# ProPrj_OpenHaldexC6_2025-10-16.net
KiCad netlist of a schematic drawn in EasyEDA Pro
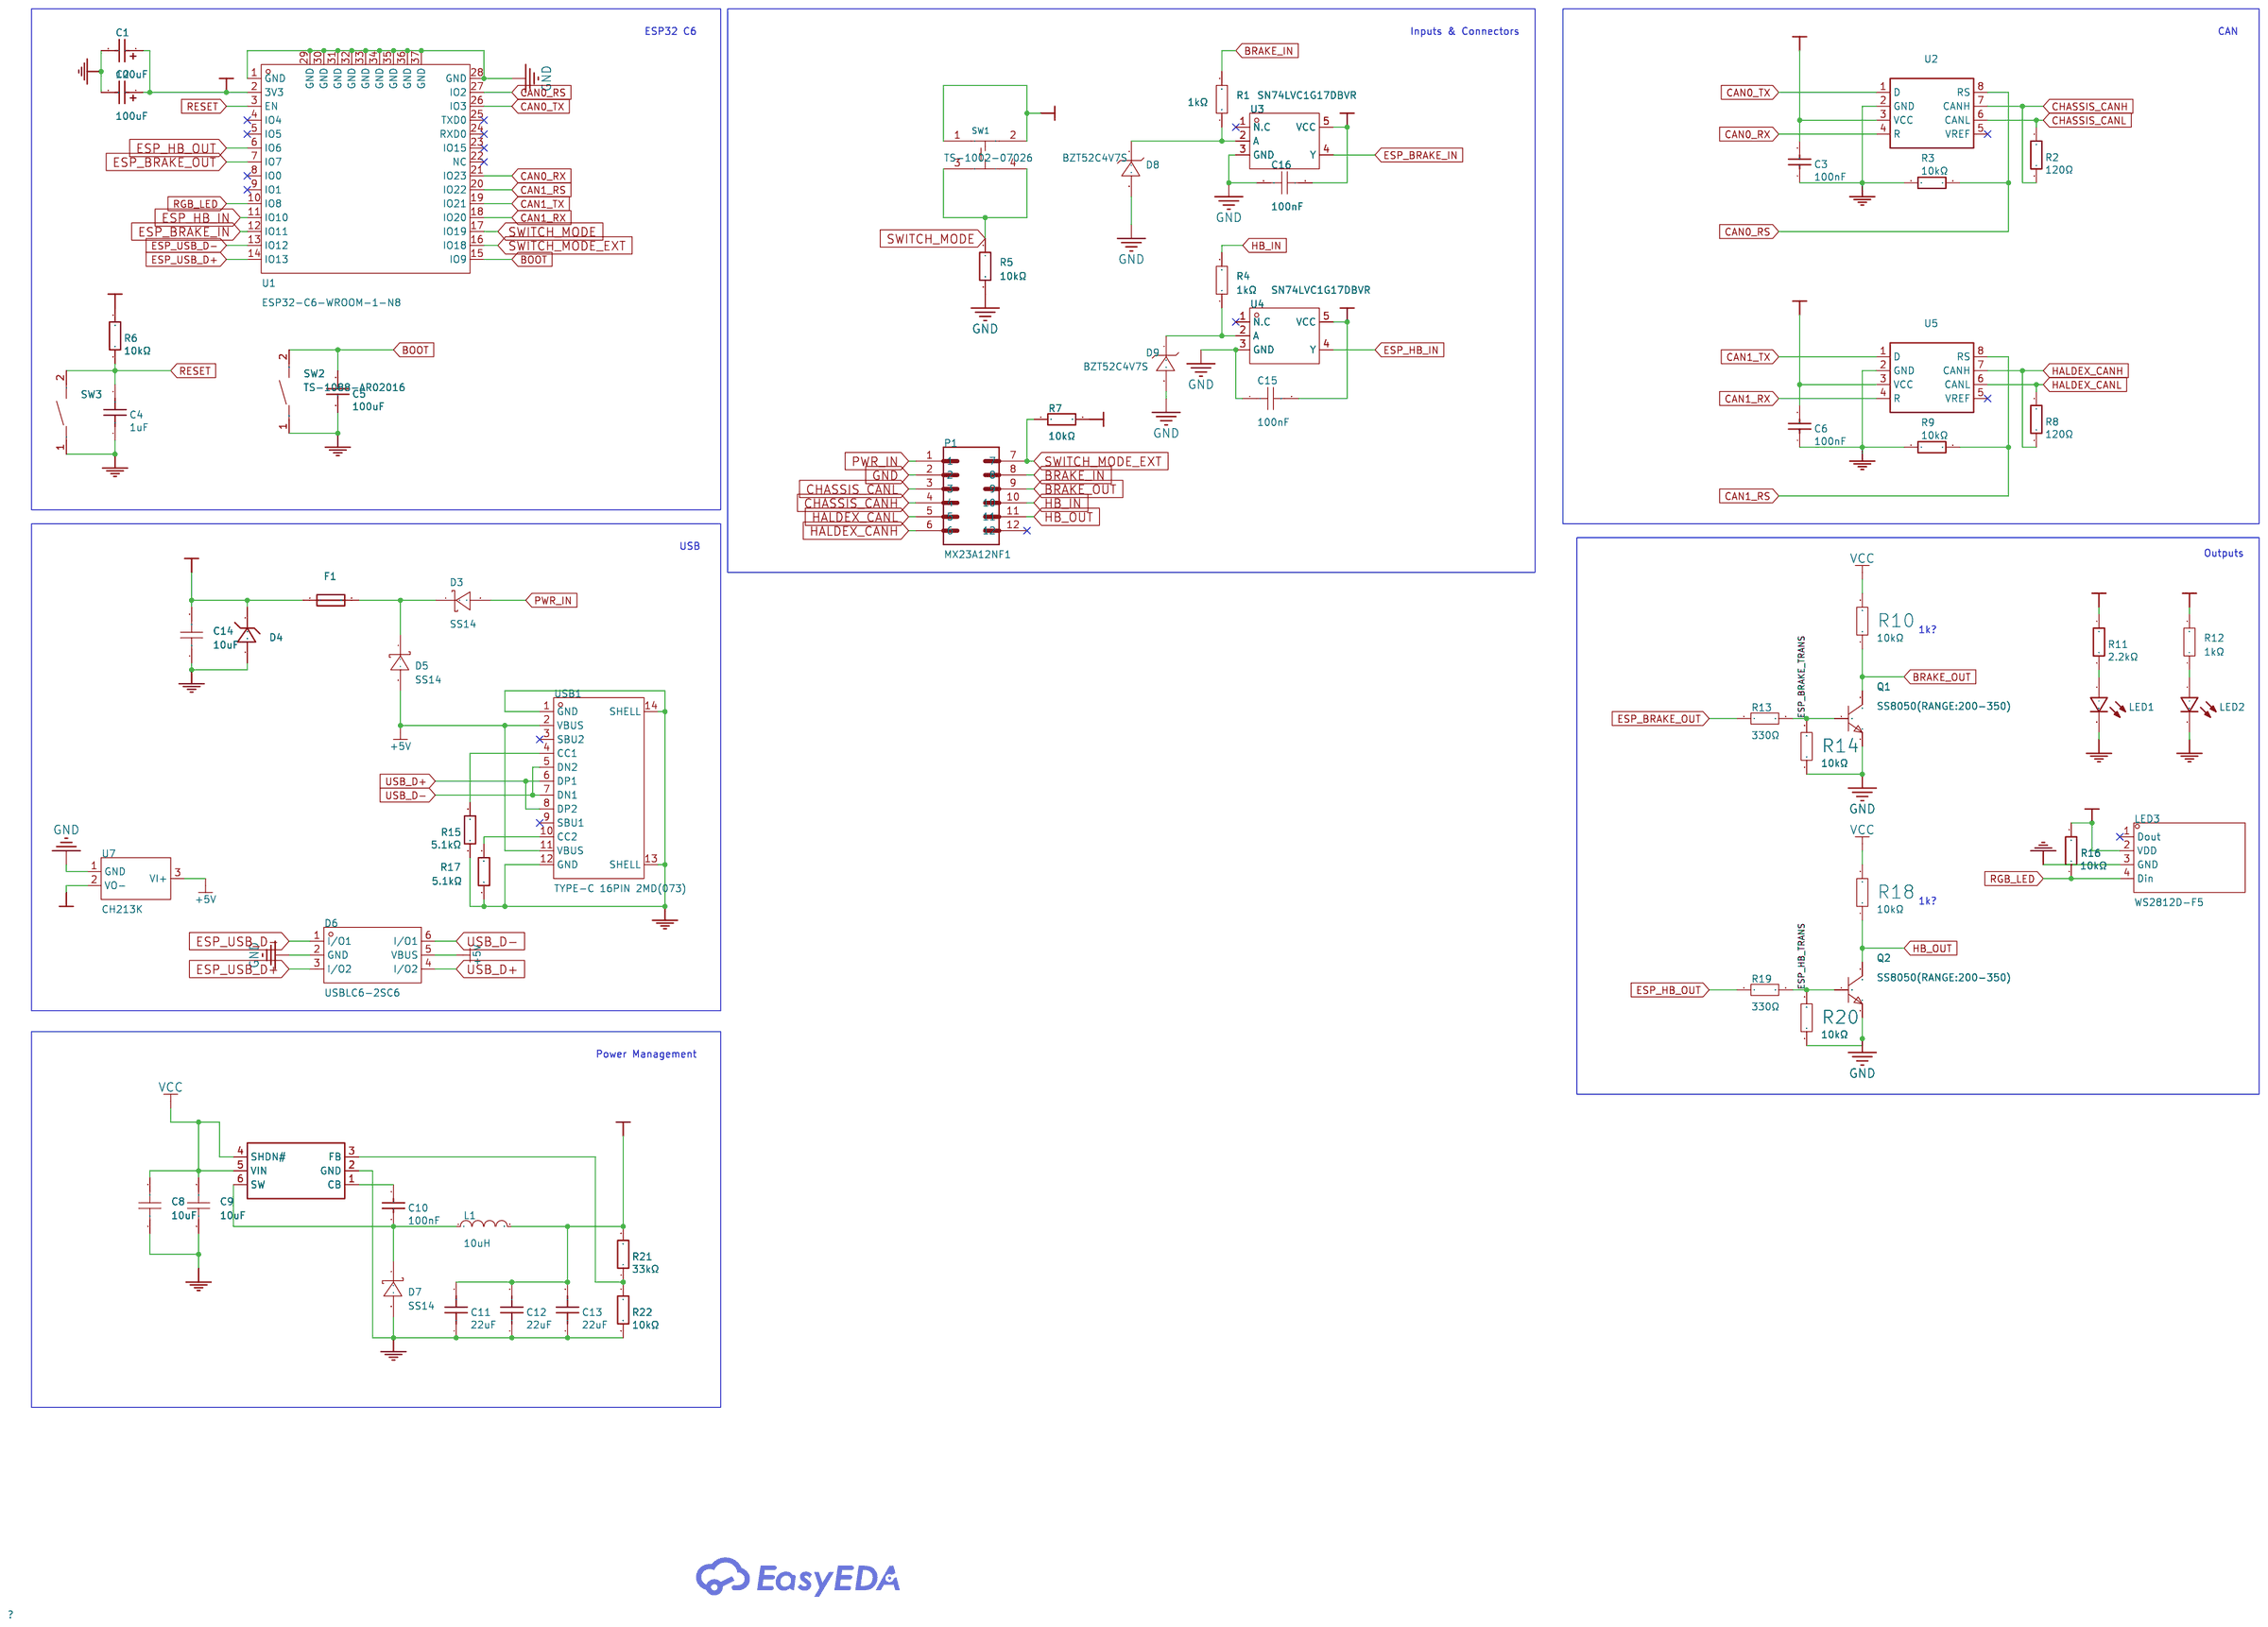
[diagram p0: schematic sheet]

(export (version "E")
  (design (tool "Eeschema 10.0.6"))
  (components
    (comp (ref "C1")
      (value "100uF")
      (fields (field (name "Manufacturer Part") "TAJB107K006RNJ") (field (name "Manufacturer") "Kyocera AVX"))
      (libsource (lib "easyedapro") (part "100uF"))
    )
    (comp (ref "C2")
      (value "100uF")
      (fields (field (name "Manufacturer Part") "TAJB107K006RNJ") (field (name "Manufacturer") "Kyocera AVX"))
      (libsource (lib "easyedapro") (part "100uF"))
    )
    (comp (ref "C3")
      (value "100nF")
      (description "Capacitance:100nF Tolerance:±10% Tolerance:±10% Voltage Rating:16V Temperature Coefficient:X7R")
      (fields (field (name "Manufacturer Part") "CL05B104KO5NNNC") (field (name "Manufacturer") "SAMSUNG"))
      (libsource (lib "easyedapro") (part "100nF"))
    )
    (comp (ref "C4")
      (value "1uF")
      (description "Capacitance:1uF Tolerance:±10% Tolerance:±10% Voltage Rating:25V Temperature Coefficient:X5R")
      (fields (field (name "Manufacturer Part") "CL05A105KA5NQNC") (field (name "Manufacturer") "SAMSUNG"))
      (libsource (lib "easyedapro") (part "1uF"))
    )
    (comp (ref "C5")
      (value "100uF")
      (fields (field (name "Manufacturer Part") "CL05B104KO5NNNC") (field (name "Manufacturer") "SAMSUNG"))
      (libsource (lib "easyedapro") (part "100nF"))
    )
    (comp (ref "C6")
      (value "100nF")
      (description "Capacitance:100nF Tolerance:±10% Tolerance:±10% Voltage Rating:16V Temperature Coefficient:X7R")
      (fields (field (name "Manufacturer Part") "CL05B104KO5NNNC") (field (name "Manufacturer") "SAMSUNG"))
      (libsource (lib "easyedapro") (part "100nF"))
    )
    (comp (ref "C8")
      (value "10uF")
      (footprint "easyedapro:C1206")
      (description "Capacitance:10uF Tolerance:±10% Tolerance:±10% Voltage Rating:35V Temperature Coefficient:-")
      (fields
        (field (name "Manufacturer Part") "CS3216X7R106K350NRI")
        (field (name "Manufacturer") "SAMWHA(三和)")
      )
      (libsource (lib "easyedapro") (part "CS3216X7R106K350NRI"))
    )
    (comp (ref "C9")
      (value "10uF")
      (footprint "easyedapro:C1206")
      (description "Capacitance:10uF Tolerance:±10% Tolerance:±10% Voltage Rating:35V Temperature Coefficient:-")
      (fields
        (field (name "Manufacturer Part") "CS3216X7R106K350NRI")
        (field (name "Manufacturer") "SAMWHA(三和)")
      )
      (libsource (lib "easyedapro") (part "CS3216X7R106K350NRI"))
    )
    (comp (ref "C10")
      (value "100nF")
      (description "Capacitance:100nF Tolerance:±10% Tolerance:±10% Voltage Rating:16V Temperature Coefficient:X7R")
      (libsource (lib "easyedapro") (part "100nF"))
    )
    (comp (ref "C11")
      (value "22uF")
      (description "Capacitance:22uF Tolerance:±20% Tolerance:±20% Voltage Rating:6.3V Temperature Coefficient:X5R")
      (libsource (lib "easyedapro") (part "22uF"))
    )
    (comp (ref "C12")
      (value "22uF")
      (description "Capacitance:22uF Tolerance:±20% Tolerance:±20% Voltage Rating:6.3V Temperature Coefficient:X5R")
      (libsource (lib "easyedapro") (part "22uF"))
    )
    (comp (ref "C13")
      (value "22uF")
      (description "Capacitance:22uF Tolerance:±20% Tolerance:±20% Voltage Rating:6.3V Temperature Coefficient:X5R")
      (libsource (lib "easyedapro") (part "22uF"))
    )
    (comp (ref "C14")
      (value "10uF")
      (footprint "easyedapro:C1206")
      (description "Capacitance:10uF Tolerance:±10% Tolerance:±10% Voltage Rating:35V Temperature Coefficient:-")
      (fields
        (field (name "Manufacturer Part") "CS3216X7R106K350NRI")
        (field (name "Manufacturer") "SAMWHA(三和)")
      )
      (libsource (lib "easyedapro") (part "CS3216X7R106K350NRI"))
    )
    (comp (ref "C15")
      (value "100nF")
      (footprint "easyedapro:C0603")
      (description "Capacitance:100nF Tolerance:±10% Tolerance:±10% Voltage Rating:50V Temperature Coefficient:X7R")
      (fields
        (field (name "Manufacturer Part") "CC0603KRX7R9BB104")
        (field (name "Manufacturer") "YAGEO(国巨)")
      )
      (libsource (lib "easyedapro") (part "CC0603KRX7R9BB104"))
    )
    (comp (ref "C16")
      (value "100nF")
      (footprint "easyedapro:C0603")
      (description "Capacitance:100nF Tolerance:±10% Tolerance:±10% Voltage Rating:50V Temperature Coefficient:X7R")
      (fields
        (field (name "Manufacturer Part") "CC0603KRX7R9BB104")
        (field (name "Manufacturer") "YAGEO(国巨)")
      )
      (libsource (lib "easyedapro") (part "CC0603KRX7R9BB104"))
    )
    (comp (ref "D3")
      (value "SS14")
      (footprint "easyedapro:SMA_L4.2-W2.6-LS5.0-RD_1")
      (fields (field (name "Manufacturer") "MDD(辰达半导体)"))
      (libsource (lib "easyedapro") (part "SS14"))
    )
    (comp (ref "D4")
      (value "SMF30A")
      (fields (field (name "Manufacturer") "DOWO"))
      (libsource (lib "easyedapro") (part "SMF30A"))
    )
    (comp (ref "D5")
      (value "SS14")
      (footprint "easyedapro:SMA_L4.2-W2.6-LS5.0-RD_1")
      (fields (field (name "Manufacturer") "MDD(辰达半导体)"))
      (libsource (lib "easyedapro") (part "SS14"))
    )
    (comp (ref "D6")
      (value "USBLC6-2SC6")
      (footprint "easyedapro:SOT-23-6_L2.9-W1.6-P0.95-LS2.8-BL")
      (description "Maximum Clamping Voltage:15V Breakdown Voltage:6V Number of Lines:双路 Type:ESD")
      (fields (field (name "Manufacturer") "UMW(友台半导体)"))
      (libsource (lib "easyedapro") (part "USBLC6-2SC6_C2687116"))
    )
    (comp (ref "D7")
      (value "SS14")
      (footprint "easyedapro:SMA_L4.2-W2.6-LS5.0-RD_1")
      (fields (field (name "Manufacturer") "MDD(辰达半导体)"))
      (libsource (lib "easyedapro") (part "SS14"))
    )
    (comp (ref "D8")
      (value "BZT52C4V7S")
      (footprint "easyedapro:SOD-323_L1.8-W1.3-LS2.5-RD")
      (fields (field (name "Manufacturer") "晶导微电子"))
      (libsource (lib "easyedapro") (part "BZT52C4V7S_C353517"))
    )
    (comp (ref "D9")
      (value "BZT52C4V7S")
      (footprint "easyedapro:SOD-323_L1.8-W1.3-LS2.5-RD")
      (fields (field (name "Manufacturer") "晶导微电子"))
      (libsource (lib "easyedapro") (part "BZT52C4V7S_C353517"))
    )
    (comp (ref "F1")
      (value "MF-MSMF110/16-2")
      (fields (field (name "Manufacturer") "BOURNS"))
      (libsource (lib "easyedapro") (part "MF-MSMF110/16-2"))
    )
    (comp (ref "L1")
      (value "10uH")
      (footprint "easyedapro:IND-SMD_L6.0-W6.0_FNR60XXS")
      (fields (field (name "Manufacturer Part") "FNR6045S100MT") (field (name "Manufacturer") "cjiang(长江微电)"))
      (libsource (lib "easyedapro") (part "FNR6045S100MT"))
    )
    (comp (ref "LED1")
      (value "19-217/GHC-YR1S2/3T")
      (fields (field (name "Manufacturer") "EVERLIGHT"))
      (libsource (lib "easyedapro") (part "19-217/GHC-YR1S2/3T"))
    )
    (comp (ref "LED2")
      (value "19-217/GHC-YR1S2/3T")
      (fields (field (name "Manufacturer") "EVERLIGHT"))
      (libsource (lib "easyedapro") (part "19-217/GHC-YR1S2/3T"))
    )
    (comp (ref "LED3")
      (value "WS2812D-F5")
      (footprint "easyedapro:LED-TH_4P-BD5.8-P1.30")
      (fields (field (name "Manufacturer") "worldsemi"))
      (libsource (lib "easyedapro") (part "WS2812D-F5"))
    )
    (comp (ref "P1")
      (value "MX23A12NF1")
      (fields (field (name "Manufacturer") "JAE(日本航空电子)"))
      (libsource (lib "easyedapro") (part "MX23A12NF1_MX23A12NF1_"))
    )
    (comp (ref "Q1")
      (value "SS8050(RANGE:200-350)")
      (footprint "easyedapro:SOT-23-3_L2.9-W1.3-P1.90-LS2.4-BR")
      (fields (field (name "Manufacturer") "CJ(江苏长电/长晶)"))
      (libsource (lib "easyedapro") (part "SS8050_C2150"))
    )
    (comp (ref "Q2")
      (value "SS8050(RANGE:200-350)")
      (footprint "easyedapro:SOT-23-3_L2.9-W1.3-P1.90-LS2.4-BR")
      (fields (field (name "Manufacturer") "CJ(江苏长电/长晶)"))
      (libsource (lib "easyedapro") (part "SS8050_C2150"))
    )
    (comp (ref "R1")
      (value "1kΩ")
      (footprint "easyedapro:R0603")
      (fields
        (field (name "Manufacturer Part") "0603WAF1001T5E")
        (field (name "Manufacturer") "UNI-ROYAL(厚声)")
      )
      (libsource (lib "easyedapro") (part "0603WAF1001T5E"))
    )
    (comp (ref "R2")
      (value "120Ω")
      (fields (field (name "Manufacturer Part") "RTT061200FTP") (field (name "Manufacturer") "RALEC"))
      (libsource (lib "easyedapro") (part "120"))
    )
    (comp (ref "R3")
      (value "10kΩ")
      (fields (field (name "Manufacturer Part") "0402WGF1002TCE") (field (name "Manufacturer") "UniOhm"))
      (libsource (lib "") (part "10K_2"))
    )
    (comp (ref "R4")
      (value "1kΩ")
      (footprint "easyedapro:R0603")
      (fields
        (field (name "Manufacturer Part") "0603WAF1001T5E")
        (field (name "Manufacturer") "UNI-ROYAL(厚声)")
      )
      (libsource (lib "easyedapro") (part "0603WAF1001T5E"))
    )
    (comp (ref "R5")
      (value "10kΩ")
      (fields (field (name "Manufacturer Part") "0402WGF1002TCE") (field (name "Manufacturer") "UniOhm"))
      (libsource (lib "easyedapro") (part "10K"))
    )
    (comp (ref "R6")
      (value "10kΩ")
      (fields (field (name "Manufacturer Part") "0402WGF1002TCE") (field (name "Manufacturer") "UniOhm"))
      (libsource (lib "easyedapro") (part "10K"))
    )
    (comp (ref "R7")
      (value "10kΩ")
      (fields (field (name "Manufacturer Part") "0402WGF1002TCE") (field (name "Manufacturer") "UniOhm"))
      (libsource (lib "easyedapro") (part "10K"))
    )
    (comp (ref "R8")
      (value "120Ω")
      (fields (field (name "Manufacturer Part") "RTT061200FTP") (field (name "Manufacturer") "RALEC"))
      (libsource (lib "easyedapro") (part "120"))
    )
    (comp (ref "R9")
      (value "10kΩ")
      (fields (field (name "Manufacturer Part") "0402WGF1002TCE") (field (name "Manufacturer") "UniOhm"))
      (libsource (lib "") (part "10K_2"))
    )
    (comp (ref "R10")
      (value "10kΩ")
      (footprint "easyedapro:R0603")
      (fields
        (field (name "Manufacturer Part") "0603WAF1002T5E")
        (field (name "Manufacturer") "UNI-ROYAL(厚声)")
      )
      (libsource (lib "easyedapro") (part "0603WAF1002T5E"))
    )
    (comp (ref "R11")
      (value "2.2kΩ")
      (fields (field (name "Manufacturer Part") "0402WGF2201TCE") (field (name "Manufacturer") "UniOhm"))
      (libsource (lib "easyedapro") (part "2.2K"))
    )
    (comp (ref "R12")
      (value "1kΩ")
      (footprint "easyedapro:R0402")
      (fields
        (field (name "Manufacturer Part") "0402WGF1001TCE")
        (field (name "Manufacturer") "UNI-ROYAL(厚声)")
      )
      (libsource (lib "easyedapro") (part "0402WGF1001TCE"))
    )
    (comp (ref "R13")
      (value "330Ω")
      (footprint "easyedapro:R0603")
      (fields
        (field (name "Manufacturer Part") "0603WAF3300T5E")
        (field (name "Manufacturer") "UNI-ROYAL(厚声)")
      )
      (libsource (lib "easyedapro") (part "0603WAF3300T5E"))
    )
    (comp (ref "R14")
      (value "10kΩ")
      (footprint "easyedapro:R0603")
      (fields
        (field (name "Manufacturer Part") "0603WAF1002T5E")
        (field (name "Manufacturer") "UNI-ROYAL(厚声)")
      )
      (libsource (lib "easyedapro") (part "0603WAF1002T5E"))
    )
    (comp (ref "R15")
      (value "5.1kΩ")
      (fields (field (name "Manufacturer Part") "0402WGF5101TCE") (field (name "Manufacturer") "UniOhm"))
      (libsource (lib "easyedapro") (part "5.1K"))
    )
    (comp (ref "R16")
      (value "10kΩ")
      (fields (field (name "Manufacturer Part") "0402WGF1002TCE") (field (name "Manufacturer") "UniOhm"))
      (libsource (lib "easyedapro") (part "10K"))
    )
    (comp (ref "R17")
      (value "5.1kΩ")
      (fields (field (name "Manufacturer Part") "0402WGF5101TCE") (field (name "Manufacturer") "UniOhm"))
      (libsource (lib "easyedapro") (part "5.1K"))
    )
    (comp (ref "R18")
      (value "10kΩ")
      (footprint "easyedapro:R0603")
      (fields
        (field (name "Manufacturer Part") "0603WAF1002T5E")
        (field (name "Manufacturer") "UNI-ROYAL(厚声)")
      )
      (libsource (lib "easyedapro") (part "0603WAF1002T5E"))
    )
    (comp (ref "R19")
      (value "330Ω")
      (footprint "easyedapro:R0603")
      (fields
        (field (name "Manufacturer Part") "0603WAF3300T5E")
        (field (name "Manufacturer") "UNI-ROYAL(厚声)")
      )
      (libsource (lib "easyedapro") (part "0603WAF3300T5E"))
    )
    (comp (ref "R20")
      (value "10kΩ")
      (footprint "easyedapro:R0603")
      (fields
        (field (name "Manufacturer Part") "0603WAF1002T5E")
        (field (name "Manufacturer") "UNI-ROYAL(厚声)")
      )
      (libsource (lib "easyedapro") (part "0603WAF1002T5E"))
    )
    (comp (ref "R21") (value "33kΩ") (libsource (lib "easyedapro") (part "33K")))
    (comp (ref "R22") (value "10kΩ") (libsource (lib "") (part "10K_1")))
    (comp (ref "SW1")
      (value "TS-1002-07026")
      (footprint "easyedapro:SW-TH_4P-L6.0-W6.0-P4.50-LS6.5")
      (fields (field (name "Manufacturer") "XUNPU(讯普)"))
      (libsource (lib "easyedapro") (part "TS-1002-07026"))
    )
    (comp (ref "SW2")
      (value "TS-1088-AR02016")
      (footprint "easyedapro:SW-SMD_L3.9-W3.0-P4.45")
      (fields (field (name "Manufacturer") "XUNPU(讯普)"))
      (libsource (lib "easyedapro") (part "TS-1088-AR02016"))
    )
    (comp (ref "SW3")
      (value "TS-1088-AR02016")
      (footprint "easyedapro:SW-SMD_L3.9-W3.0-P4.45")
      (fields (field (name "Manufacturer") "XUNPU(讯普)"))
      (libsource (lib "easyedapro") (part "TS-1088-AR02016"))
    )
    (comp (ref "U1")
      (value "ESP32-C6-WROOM-1-N8")
      (footprint "easyedapro:WIRELM-SMD_ESP32-C6-WROOM-1")
      (fields (field (name "Manufacturer") "ESPRESSIF(乐鑫)"))
      (libsource (lib "easyedapro") (part "ESP32-C6-WROOM-1-N8"))
    )
    (comp (ref "U2")
      (value "SN65HVD230DR")
      (fields (field (name "Manufacturer") "TI"))
      (libsource (lib "easyedapro") (part "SN65HVD230DR"))
    )
    (comp (ref "U3")
      (value "SN74LVC1G17DBVR")
      (footprint "easyedapro:SOT-23-5_L3.0-W1.5-P0.95-LS2.8-BL")
      (fields (field (name "Manufacturer") "TECH PUBLIC(台舟)"))
      (libsource (lib "easyedapro") (part "SN74LVC1G17DBVR_C19829662"))
    )
    (comp (ref "U4")
      (value "SN74LVC1G17DBVR")
      (footprint "easyedapro:SOT-23-5_L3.0-W1.5-P0.95-LS2.8-BL")
      (fields (field (name "Manufacturer") "TECH PUBLIC(台舟)"))
      (libsource (lib "easyedapro") (part "SN74LVC1G17DBVR_C19829662"))
    )
    (comp (ref "U5")
      (value "SN65HVD230DR")
      (fields (field (name "Manufacturer") "TI"))
      (libsource (lib "easyedapro") (part "SN65HVD230DR"))
    )
    (comp (ref "U6") (value "LMR14006XDDCR") (libsource (lib "easyedapro") (part "LMR14006XDDCR")))
    (comp (ref "U7")
      (value "CH213K")
      (footprint "easyedapro:SOT-23-3_L2.9-W1.6-P1.90-LS2.8-BR")
      (fields (field (name "Manufacturer") "WCH(南京沁恒)"))
      (libsource (lib "easyedapro") (part "CH213K"))
    )
    (comp (ref "USB1")
      (value "TYPE-C 16PIN 2MD(073)")
      (footprint "easyedapro:USB-C-SMD_TYPE-C-6PIN-2MD-073")
      (fields (field (name "Manufacturer") "SHOU HAN(首韩)"))
      (libsource (lib "easyedapro") (part "TYPE-C 16PIN 2MD(073)"))
    )
  )
  (nets
    (net (code "1") (name "+5V") (class "Default")
      (node (ref "D5") (pin "2") (pinfunction "A_2") (pintype "unspecified"))
      (node (ref "D6") (pin "5") (pinfunction "VBUS_5") (pintype "unspecified"))
      (node (ref "U7") (pin "3") (pinfunction "VI+_3") (pintype "unspecified"))
      (node (ref "USB1") (pin "11") (pinfunction "VBUS_11") (pintype "unspecified"))
      (node (ref "USB1") (pin "2") (pinfunction "VBUS_2") (pintype "unspecified"))
    )
    (net (code "2") (name "/ESP_BRAKE_TRANS") (class "Default")
      (node (ref "Q1") (pin "1") (pinfunction "B_1") (pintype "unspecified"))
      (node (ref "R13") (pin "2") (pinfunction "2_2") (pintype "input"))
      (node (ref "R14") (pin "2") (pinfunction "2_2") (pintype "input"))
    )
    (net (code "3") (name "/ESP_HB_TRANS") (class "Default")
      (node (ref "Q2") (pin "1") (pinfunction "B_1") (pintype "unspecified"))
      (node (ref "R19") (pin "2") (pinfunction "2_2") (pintype "input"))
      (node (ref "R20") (pin "2") (pinfunction "2_2") (pintype "input"))
    )
    (net (code "4") (name "3V3") (class "Default")
      (node (ref "C1") (pin "1") (pinfunction "1_1") (pintype "input"))
      (node (ref "C11") (pin "2") (pinfunction "2_2") (pintype "unspecified"))
      (node (ref "C12") (pin "2") (pinfunction "2_2") (pintype "unspecified"))
      (node (ref "C13") (pin "2") (pinfunction "2_2") (pintype "unspecified"))
      (node (ref "C15") (pin "2") (pinfunction "2_2") (pintype "unspecified"))
      (node (ref "C16") (pin "2") (pinfunction "2_2") (pintype "unspecified"))
      (node (ref "C2") (pin "1") (pinfunction "1_1") (pintype "input"))
      (node (ref "C3") (pin "2") (pinfunction "2_2") (pintype "input"))
      (node (ref "C6") (pin "2") (pinfunction "2_2") (pintype "input"))
      (node (ref "L1") (pin "2") (pinfunction "2_2") (pintype "unspecified"))
      (node (ref "LED3") (pin "2") (pinfunction "VDD_2") (pintype "unspecified"))
      (node (ref "R12") (pin "2") (pinfunction "2_2") (pintype "input"))
      (node (ref "R16") (pin "2") (pinfunction "2_2") (pintype "input"))
      (node (ref "R21") (pin "2") (pinfunction "2_2") (pintype "input"))
      (node (ref "R6") (pin "2") (pinfunction "2_2") (pintype "input"))
      (node (ref "R7") (pin "2") (pinfunction "2_2") (pintype "input"))
      (node (ref "SW1") (pin "1") (pinfunction "1_1") (pintype "input"))
      (node (ref "SW1") (pin "2") (pinfunction "2_2") (pintype "input"))
      (node (ref "U1") (pin "2") (pinfunction "3V3_2") (pintype "unspecified"))
      (node (ref "U2") (pin "3") (pinfunction "VCC_3") (pintype "unspecified"))
      (node (ref "U3") (pin "5") (pinfunction "VCC_5") (pintype "unspecified"))
      (node (ref "U4") (pin "5") (pinfunction "VCC_5") (pintype "unspecified"))
      (node (ref "U5") (pin "3") (pinfunction "VCC_3") (pintype "unspecified"))
    )
    (net (code "5") (name "BOOT") (class "Default")
      (node (ref "C5") (pin "2") (pinfunction "2_2") (pintype "input"))
      (node (ref "SW2") (pin "2") (pinfunction "2_2") (pintype "unspecified"))
      (node (ref "U1") (pin "15") (pinfunction "IO9_15") (pintype "unspecified"))
    )
    (net (code "6") (name "BRAKE_IN") (class "Default")
      (node (ref "P1") (pin "8") (pinfunction "8_8") (pintype "unspecified"))
      (node (ref "R1") (pin "2") (pinfunction "2_2") (pintype "input"))
    )
    (net (code "7") (name "BRAKE_OUT") (class "Default")
      (node (ref "P1") (pin "9") (pinfunction "9_9") (pintype "unspecified"))
      (node (ref "Q1") (pin "3") (pinfunction "C_3") (pintype "unspecified"))
      (node (ref "R10") (pin "1") (pinfunction "1_1") (pintype "input"))
    )
    (net (code "8") (name "CAN0_RS") (class "Default")
      (node (ref "R3") (pin "2") (pinfunction "2_2") (pintype "input"))
      (node (ref "U1") (pin "27") (pinfunction "IO2_27") (pintype "unspecified"))
      (node (ref "U2") (pin "8") (pinfunction "RS_8") (pintype "unspecified"))
    )
    (net (code "9") (name "CAN0_RX") (class "Default")
      (node (ref "U1") (pin "21") (pinfunction "IO23_21") (pintype "unspecified"))
      (node (ref "U2") (pin "4") (pinfunction "R_4") (pintype "unspecified"))
    )
    (net (code "10") (name "CAN0_TX") (class "Default")
      (node (ref "U1") (pin "26") (pinfunction "IO3_26") (pintype "unspecified"))
      (node (ref "U2") (pin "1") (pinfunction "D_1") (pintype "unspecified"))
    )
    (net (code "11") (name "CAN1_RS") (class "Default")
      (node (ref "R9") (pin "2") (pinfunction "2_2") (pintype "input"))
      (node (ref "U1") (pin "20") (pinfunction "IO22_20") (pintype "unspecified"))
      (node (ref "U5") (pin "8") (pinfunction "RS_8") (pintype "unspecified"))
    )
    (net (code "12") (name "CAN1_RX") (class "Default")
      (node (ref "U1") (pin "18") (pinfunction "IO20_18") (pintype "unspecified"))
      (node (ref "U5") (pin "4") (pinfunction "R_4") (pintype "unspecified"))
    )
    (net (code "13") (name "CAN1_TX") (class "Default")
      (node (ref "U1") (pin "19") (pinfunction "IO21_19") (pintype "unspecified"))
      (node (ref "U5") (pin "1") (pinfunction "D_1") (pintype "unspecified"))
    )
    (net (code "14") (name "CHASSIS_CANH") (class "Default")
      (node (ref "P1") (pin "4") (pinfunction "4_4") (pintype "unspecified"))
      (node (ref "R2") (pin "2") (pinfunction "2_2") (pintype "unspecified"))
      (node (ref "U2") (pin "7") (pinfunction "CANH_7") (pintype "unspecified"))
    )
    (net (code "15") (name "CHASSIS_CANL") (class "Default")
      (node (ref "P1") (pin "3") (pinfunction "3_3") (pintype "unspecified"))
      (node (ref "R2") (pin "1") (pinfunction "1_1") (pintype "unspecified"))
      (node (ref "U2") (pin "6") (pinfunction "CANL_6") (pintype "unspecified"))
    )
    (net (code "16") (name "ESP_BRAKE_IN") (class "Default")
      (node (ref "U1") (pin "12") (pinfunction "IO11_12") (pintype "unspecified"))
      (node (ref "U3") (pin "4") (pinfunction "Y_4") (pintype "unspecified"))
    )
    (net (code "17") (name "ESP_BRAKE_OUT") (class "Default")
      (node (ref "R13") (pin "1") (pinfunction "1_1") (pintype "input"))
      (node (ref "U1") (pin "7") (pinfunction "IO7_7") (pintype "unspecified"))
    )
    (net (code "18") (name "ESP_HB_IN") (class "Default")
      (node (ref "U1") (pin "11") (pinfunction "IO10_11") (pintype "unspecified"))
      (node (ref "U4") (pin "4") (pinfunction "Y_4") (pintype "unspecified"))
    )
    (net (code "19") (name "ESP_HB_OUT") (class "Default")
      (node (ref "R19") (pin "1") (pinfunction "1_1") (pintype "input"))
      (node (ref "U1") (pin "6") (pinfunction "IO6_6") (pintype "unspecified"))
    )
    (net (code "20") (name "ESP_USB_D+") (class "Default")
      (node (ref "D6") (pin "3") (pinfunction "I/O2_3") (pintype "unspecified"))
      (node (ref "U1") (pin "14") (pinfunction "IO13_14") (pintype "unspecified"))
    )
    (net (code "21") (name "ESP_USB_D-") (class "Default")
      (node (ref "D6") (pin "1") (pinfunction "I/O1_1") (pintype "unspecified"))
      (node (ref "U1") (pin "13") (pinfunction "IO12_13") (pintype "unspecified"))
    )
    (net (code "22") (name "GND") (class "Default")
      (node (ref "C1") (pin "2") (pinfunction "2_2") (pintype "input"))
      (node (ref "C11") (pin "1") (pinfunction "1_1") (pintype "unspecified"))
      (node (ref "C12") (pin "1") (pinfunction "1_1") (pintype "unspecified"))
      (node (ref "C13") (pin "1") (pinfunction "1_1") (pintype "unspecified"))
      (node (ref "C14") (pin "1") (pinfunction "1_1") (pintype "unspecified"))
      (node (ref "C15") (pin "1") (pinfunction "1_1") (pintype "unspecified"))
      (node (ref "C16") (pin "1") (pinfunction "1_1") (pintype "unspecified"))
      (node (ref "C2") (pin "2") (pinfunction "2_2") (pintype "input"))
      (node (ref "C3") (pin "1") (pinfunction "1_1") (pintype "input"))
      (node (ref "C4") (pin "1") (pinfunction "1_1") (pintype "unspecified"))
      (node (ref "C5") (pin "1") (pinfunction "1_1") (pintype "input"))
      (node (ref "C6") (pin "1") (pinfunction "1_1") (pintype "input"))
      (node (ref "C8") (pin "1") (pinfunction "1_1") (pintype "unspecified"))
      (node (ref "C9") (pin "1") (pinfunction "1_1") (pintype "unspecified"))
      (node (ref "D4") (pin "2") (pinfunction "2_2") (pintype "unspecified"))
      (node (ref "D6") (pin "2") (pinfunction "GND_2") (pintype "unspecified"))
      (node (ref "D7") (pin "2") (pinfunction "A_2") (pintype "unspecified"))
      (node (ref "D8") (pin "2") (pinfunction "A_2") (pintype "unspecified"))
      (node (ref "D9") (pin "2") (pinfunction "A_2") (pintype "unspecified"))
      (node (ref "LED1") (pin "2") (pinfunction "C_2") (pintype "input"))
      (node (ref "LED2") (pin "2") (pinfunction "C_2") (pintype "input"))
      (node (ref "LED3") (pin "3") (pinfunction "GND_3") (pintype "unspecified"))
      (node (ref "P1") (pin "2") (pinfunction "2_2") (pintype "unspecified"))
      (node (ref "Q1") (pin "2") (pinfunction "E_2") (pintype "unspecified"))
      (node (ref "Q2") (pin "2") (pinfunction "E_2") (pintype "unspecified"))
      (node (ref "R14") (pin "1") (pinfunction "1_1") (pintype "input"))
      (node (ref "R15") (pin "1") (pinfunction "1_1") (pintype "input"))
      (node (ref "R17") (pin "1") (pinfunction "1_1") (pintype "input"))
      (node (ref "R20") (pin "1") (pinfunction "1_1") (pintype "input"))
      (node (ref "R22") (pin "2") (pinfunction "2_2") (pintype "input"))
      (node (ref "R3") (pin "1") (pinfunction "1_1") (pintype "input"))
      (node (ref "R5") (pin "2") (pinfunction "2_2") (pintype "input"))
      (node (ref "R9") (pin "1") (pinfunction "1_1") (pintype "input"))
      (node (ref "SW2") (pin "1") (pinfunction "1_1") (pintype "unspecified"))
      (node (ref "SW3") (pin "1") (pinfunction "1_1") (pintype "unspecified"))
      (node (ref "U1") (pin "1") (pinfunction "GND_1") (pintype "unspecified"))
      (node (ref "U1") (pin "28") (pinfunction "GND_28") (pintype "unspecified"))
      (node (ref "U1") (pin "29") (pinfunction "GND_29") (pintype "unspecified"))
      (node (ref "U1") (pin "30") (pinfunction "GND_30") (pintype "unspecified"))
      (node (ref "U1") (pin "31") (pinfunction "GND_31") (pintype "unspecified"))
      (node (ref "U1") (pin "32") (pinfunction "GND_32") (pintype "unspecified"))
      (node (ref "U1") (pin "33") (pinfunction "GND_33") (pintype "unspecified"))
      (node (ref "U1") (pin "34") (pinfunction "GND_34") (pintype "unspecified"))
      (node (ref "U1") (pin "35") (pinfunction "GND_35") (pintype "unspecified"))
      (node (ref "U1") (pin "36") (pinfunction "GND_36") (pintype "unspecified"))
      (node (ref "U1") (pin "37") (pinfunction "GND_37") (pintype "unspecified"))
      (node (ref "U2") (pin "2") (pinfunction "GND_2") (pintype "unspecified"))
      (node (ref "U3") (pin "3") (pinfunction "GND_3") (pintype "unspecified"))
      (node (ref "U4") (pin "3") (pinfunction "GND_3") (pintype "unspecified"))
      (node (ref "U5") (pin "2") (pinfunction "GND_2") (pintype "unspecified"))
      (node (ref "U6") (pin "2") (pinfunction "GND_2") (pintype "unspecified"))
      (node (ref "U7") (pin "1") (pinfunction "GND_1") (pintype "unspecified"))
      (node (ref "USB1") (pin "1") (pinfunction "GND_1") (pintype "unspecified"))
      (node (ref "USB1") (pin "12") (pinfunction "GND_12") (pintype "unspecified"))
      (node (ref "USB1") (pin "13") (pinfunction "SHELL_13") (pintype "unspecified"))
      (node (ref "USB1") (pin "14") (pinfunction "SHELL_14") (pintype "unspecified"))
    )
    (net (code "23") (name "HALDEX_CANH") (class "Default")
      (node (ref "P1") (pin "6") (pinfunction "6_6") (pintype "unspecified"))
      (node (ref "R8") (pin "2") (pinfunction "2_2") (pintype "unspecified"))
      (node (ref "U5") (pin "7") (pinfunction "CANH_7") (pintype "unspecified"))
    )
    (net (code "24") (name "HALDEX_CANL") (class "Default")
      (node (ref "P1") (pin "5") (pinfunction "5_5") (pintype "unspecified"))
      (node (ref "R8") (pin "1") (pinfunction "1_1") (pintype "unspecified"))
      (node (ref "U5") (pin "6") (pinfunction "CANL_6") (pintype "unspecified"))
    )
    (net (code "25") (name "HB_IN") (class "Default")
      (node (ref "P1") (pin "10") (pinfunction "10_10") (pintype "unspecified"))
      (node (ref "R4") (pin "2") (pinfunction "2_2") (pintype "input"))
    )
    (net (code "26") (name "HB_OUT") (class "Default")
      (node (ref "P1") (pin "11") (pinfunction "11_11") (pintype "unspecified"))
      (node (ref "Q2") (pin "3") (pinfunction "C_3") (pintype "unspecified"))
      (node (ref "R18") (pin "1") (pinfunction "1_1") (pintype "input"))
    )
    (net (code "27") (name "Net-(D3-K)") (class "Default")
      (node (ref "D3") (pin "1") (pinfunction "K_1") (pintype "unspecified"))
      (node (ref "D5") (pin "1") (pinfunction "K_1") (pintype "unspecified"))
      (node (ref "F1") (pin "2") (pinfunction "2_2") (pintype "unspecified"))
    )
    (net (code "28") (name "Net-(D7-K)") (class "Default")
      (node (ref "C10") (pin "1") (pinfunction "1_1") (pintype "input"))
      (node (ref "D7") (pin "1") (pinfunction "K_1") (pintype "unspecified"))
      (node (ref "L1") (pin "1") (pinfunction "1_1") (pintype "unspecified"))
      (node (ref "U6") (pin "6") (pinfunction "SW_6") (pintype "unspecified"))
    )
    (net (code "29") (name "Net-(D8-K)") (class "Default")
      (node (ref "D8") (pin "1") (pinfunction "K_1") (pintype "unspecified"))
      (node (ref "R1") (pin "1") (pinfunction "1_1") (pintype "input"))
      (node (ref "U3") (pin "2") (pinfunction "A_2") (pintype "unspecified"))
    )
    (net (code "30") (name "Net-(D9-K)") (class "Default")
      (node (ref "D9") (pin "1") (pinfunction "K_1") (pintype "unspecified"))
      (node (ref "R4") (pin "1") (pinfunction "1_1") (pintype "input"))
      (node (ref "U4") (pin "2") (pinfunction "A_2") (pintype "unspecified"))
    )
    (net (code "31") (name "Net-(LED1-A)") (class "Default")
      (node (ref "LED1") (pin "1") (pinfunction "A_1") (pintype "input"))
      (node (ref "R11") (pin "2") (pinfunction "2_2") (pintype "input"))
    )
    (net (code "32") (name "Net-(LED2-A)") (class "Default")
      (node (ref "LED2") (pin "1") (pinfunction "A_1") (pintype "input"))
      (node (ref "R12") (pin "1") (pinfunction "1_1") (pintype "input"))
    )
    (net (code "33") (name "Net-(U6-CB)") (class "Default")
      (node (ref "C10") (pin "2") (pinfunction "2_2") (pintype "input"))
      (node (ref "U6") (pin "1") (pinfunction "CB_1") (pintype "unspecified"))
    )
    (net (code "34") (name "Net-(U6-FB)") (class "Default")
      (node (ref "R21") (pin "1") (pinfunction "1_1") (pintype "input"))
      (node (ref "R22") (pin "1") (pinfunction "1_1") (pintype "input"))
      (node (ref "U6") (pin "3") (pinfunction "FB_3") (pintype "unspecified"))
    )
    (net (code "35") (name "Net-(USB1-CC1)") (class "Default")
      (node (ref "R15") (pin "2") (pinfunction "2_2") (pintype "input"))
      (node (ref "USB1") (pin "4") (pinfunction "CC1_4") (pintype "unspecified"))
    )
    (net (code "36") (name "Net-(USB1-CC2)") (class "Default")
      (node (ref "R17") (pin "2") (pinfunction "2_2") (pintype "input"))
      (node (ref "USB1") (pin "10") (pinfunction "CC2_10") (pintype "unspecified"))
    )
    (net (code "37") (name "PWR_IN") (class "Default")
      (node (ref "D3") (pin "2") (pinfunction "A_2") (pintype "unspecified"))
      (node (ref "P1") (pin "1") (pinfunction "1_1") (pintype "unspecified"))
    )
    (net (code "38") (name "RESET") (class "Default")
      (node (ref "C4") (pin "2") (pinfunction "2_2") (pintype "unspecified"))
      (node (ref "R6") (pin "1") (pinfunction "1_1") (pintype "input"))
      (node (ref "SW3") (pin "2") (pinfunction "2_2") (pintype "unspecified"))
      (node (ref "U1") (pin "3") (pinfunction "EN_3") (pintype "unspecified"))
    )
    (net (code "39") (name "RGB_LED") (class "Default")
      (node (ref "LED3") (pin "4") (pinfunction "Din_4") (pintype "unspecified"))
      (node (ref "R16") (pin "1") (pinfunction "1_1") (pintype "input"))
      (node (ref "U1") (pin "10") (pinfunction "IO8_10") (pintype "unspecified"))
    )
    (net (code "40") (name "SWITCH_MODE") (class "Default")
      (node (ref "R5") (pin "1") (pinfunction "1_1") (pintype "input"))
      (node (ref "SW1") (pin "3") (pinfunction "3_3") (pintype "input"))
      (node (ref "SW1") (pin "4") (pinfunction "4_4") (pintype "input"))
      (node (ref "U1") (pin "17") (pinfunction "IO19_17") (pintype "unspecified"))
    )
    (net (code "41") (name "SWITCH_MODE_EXT") (class "Default")
      (node (ref "P1") (pin "7") (pinfunction "7_7") (pintype "unspecified"))
      (node (ref "R7") (pin "1") (pinfunction "1_1") (pintype "input"))
      (node (ref "U1") (pin "16") (pinfunction "IO18_16") (pintype "unspecified"))
    )
    (net (code "42") (name "USB_D+") (class "Default")
      (node (ref "D6") (pin "4") (pinfunction "I/O2_4") (pintype "unspecified"))
      (node (ref "USB1") (pin "6") (pinfunction "DP1_6") (pintype "unspecified"))
      (node (ref "USB1") (pin "8") (pinfunction "DP2_8") (pintype "unspecified"))
    )
    (net (code "43") (name "USB_D-") (class "Default")
      (node (ref "D6") (pin "6") (pinfunction "I/O1_6") (pintype "unspecified"))
      (node (ref "USB1") (pin "5") (pinfunction "DN2_5") (pintype "unspecified"))
      (node (ref "USB1") (pin "7") (pinfunction "DN1_7") (pintype "unspecified"))
    )
    (net (code "44") (name "VCC") (class "Default")
      (node (ref "C14") (pin "2") (pinfunction "2_2") (pintype "unspecified"))
      (node (ref "C8") (pin "2") (pinfunction "2_2") (pintype "unspecified"))
      (node (ref "C9") (pin "2") (pinfunction "2_2") (pintype "unspecified"))
      (node (ref "D4") (pin "1") (pinfunction "1_1") (pintype "unspecified"))
      (node (ref "F1") (pin "1") (pinfunction "1_1") (pintype "unspecified"))
      (node (ref "R10") (pin "2") (pinfunction "2_2") (pintype "input"))
      (node (ref "R11") (pin "1") (pinfunction "1_1") (pintype "input"))
      (node (ref "R18") (pin "2") (pinfunction "2_2") (pintype "input"))
      (node (ref "U6") (pin "4") (pinfunction "SHDN#_4") (pintype "unspecified"))
      (node (ref "U6") (pin "5") (pinfunction "VIN_5") (pintype "unspecified"))
      (node (ref "U7") (pin "2") (pinfunction "VO-_2") (pintype "unspecified"))
    )
    (net (code "45") (name "unconnected-(LED3-Dout-Pad1)") (class "Default")
      (node (ref "LED3") (pin "1") (pinfunction "Dout_1") (pintype "unspecified+no_connect"))
    )
    (net (code "46") (name "unconnected-(P1-Pad12)") (class "Default")
      (node (ref "P1") (pin "12") (pinfunction "12_12") (pintype "unspecified+no_connect"))
    )
    (net (code "47") (name "unconnected-(U1-IO0-Pad8)") (class "Default")
      (node (ref "U1") (pin "8") (pinfunction "IO0_8") (pintype "unspecified+no_connect"))
    )
    (net (code "48") (name "unconnected-(U1-IO1-Pad9)") (class "Default")
      (node (ref "U1") (pin "9") (pinfunction "IO1_9") (pintype "unspecified+no_connect"))
    )
    (net (code "49") (name "unconnected-(U1-IO4-Pad4)") (class "Default")
      (node (ref "U1") (pin "4") (pinfunction "IO4_4") (pintype "unspecified+no_connect"))
    )
    (net (code "50") (name "unconnected-(U1-IO5-Pad5)") (class "Default")
      (node (ref "U1") (pin "5") (pinfunction "IO5_5") (pintype "unspecified+no_connect"))
    )
    (net (code "51") (name "unconnected-(U1-IO15-Pad23)") (class "Default")
      (node (ref "U1") (pin "23") (pinfunction "IO15_23") (pintype "unspecified+no_connect"))
    )
    (net (code "52") (name "unconnected-(U1-NC-Pad22)") (class "Default")
      (node (ref "U1") (pin "22") (pinfunction "NC_22") (pintype "unspecified+no_connect"))
    )
    (net (code "53") (name "unconnected-(U1-RXD0-Pad24)") (class "Default")
      (node (ref "U1") (pin "24") (pinfunction "RXD0_24") (pintype "unspecified+no_connect"))
    )
    (net (code "54") (name "unconnected-(U1-TXD0-Pad25)") (class "Default")
      (node (ref "U1") (pin "25") (pinfunction "TXD0_25") (pintype "unspecified+no_connect"))
    )
    (net (code "55") (name "unconnected-(U2-VREF-Pad5)") (class "Default")
      (node (ref "U2") (pin "5") (pinfunction "VREF_5") (pintype "unspecified+no_connect"))
    )
    (net (code "56") (name "unconnected-(U3-N.C-Pad1)") (class "Default")
      (node (ref "U3") (pin "1") (pinfunction "N.C_1") (pintype "unspecified+no_connect"))
    )
    (net (code "57") (name "unconnected-(U4-N.C-Pad1)") (class "Default")
      (node (ref "U4") (pin "1") (pinfunction "N.C_1") (pintype "unspecified+no_connect"))
    )
    (net (code "58") (name "unconnected-(U5-VREF-Pad5)") (class "Default")
      (node (ref "U5") (pin "5") (pinfunction "VREF_5") (pintype "unspecified+no_connect"))
    )
    (net (code "59") (name "unconnected-(USB1-SBU1-Pad9)") (class "Default")
      (node (ref "USB1") (pin "9") (pinfunction "SBU1_9") (pintype "unspecified+no_connect"))
    )
    (net (code "60") (name "unconnected-(USB1-SBU2-Pad3)") (class "Default")
      (node (ref "USB1") (pin "3") (pinfunction "SBU2_3") (pintype "unspecified+no_connect"))
    )
  )
)
